# sensor.net
KiCad netlist of a schematic drawn in Altium Designer
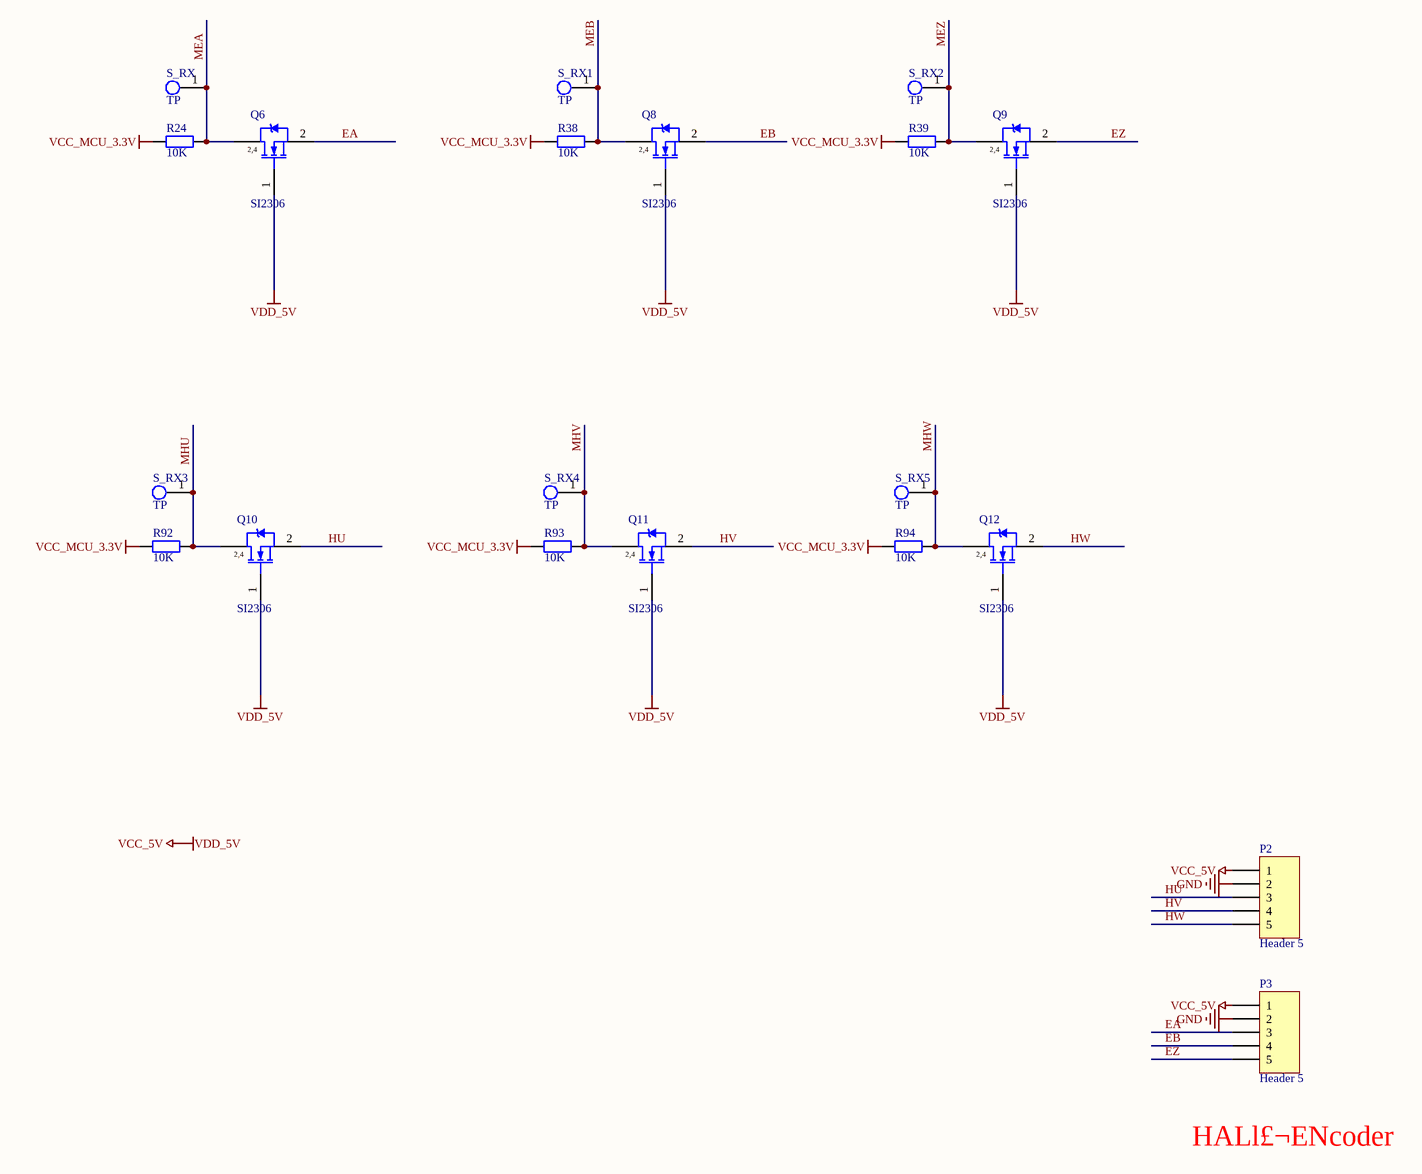
[diagram p0: sensor.SchDoc]

(export (version "E")
  (design (tool "Eeschema 10.0.6"))
  (components
    (comp (ref "P2")
      (value "Header 5")
      (footprint "HDR1X5")
      (description "Header, 5-Pin")
      (fields (field (name "PUBLISHER") "Altium Limited"))
      (libsource (lib "Miscellaneous Connectors") (part "Header 5"))
    )
    (comp (ref "P3")
      (value "Header 5")
      (footprint "HDR1X5")
      (description "Header, 5-Pin")
      (fields (field (name "PUBLISHER") "Altium Limited"))
      (libsource (lib "Miscellaneous Connectors") (part "Header 5"))
    )
    (comp (ref "Q6")
      (value "SI2306")
      (footprint "Pcblib_20110825:SOT23-3")
      (description "BUK92150-55A")
      (fields (field (name "PUBLISHER") "Altium Limited"))
      (libsource (lib "Schlib1") (part "BUK92150-55A"))
    )
    (comp (ref "Q8")
      (value "SI2306")
      (footprint "SOT23-3")
      (description "BUK92150-55A")
      (fields (field (name "PUBLISHER") "Altium Limited"))
      (libsource (lib "Schlib1") (part "BUK92150-55A"))
    )
    (comp (ref "Q9")
      (value "SI2306")
      (footprint "Pcblib_20110825:SOT23-3")
      (description "BUK92150-55A")
      (fields (field (name "PUBLISHER") "Altium Limited"))
      (libsource (lib "Schlib1") (part "BUK92150-55A"))
    )
    (comp (ref "Q10")
      (value "SI2306")
      (footprint "Pcblib_20110825:SOT23-3")
      (description "BUK92150-55A")
      (fields (field (name "PUBLISHER") "Altium Limited"))
      (libsource (lib "Schlib1") (part "BUK92150-55A"))
    )
    (comp (ref "Q11")
      (value "SI2306")
      (footprint "Pcblib_20110825:SOT23-3")
      (description "BUK92150-55A")
      (fields (field (name "PUBLISHER") "Altium Limited"))
      (libsource (lib "Schlib1") (part "BUK92150-55A"))
    )
    (comp (ref "Q12")
      (value "SI2306")
      (footprint "Pcblib_20110825:SOT23-3")
      (description "BUK92150-55A")
      (fields (field (name "PUBLISHER") "Altium Limited"))
      (libsource (lib "Schlib1") (part "BUK92150-55A"))
    )
    (comp (ref "R24")
      (value "10K")
      (footprint "Pcblib_20110825:0603R")
      (description "Resistor")
      (fields (field (name "PUBLISHER") "Altium Limited"))
      (libsource (lib "Miscellaneous Devices") (part "Res2"))
    )
    (comp (ref "R38")
      (value "10K")
      (footprint "Pcblib_20110825:0603R")
      (description "Resistor")
      (fields (field (name "PUBLISHER") "Altium Limited"))
      (libsource (lib "Miscellaneous Devices") (part "Res2"))
    )
    (comp (ref "R39")
      (value "10K")
      (footprint "Pcblib_20110825:0603R")
      (description "Resistor")
      (fields (field (name "PUBLISHER") "Altium Limited"))
      (libsource (lib "Miscellaneous Devices") (part "Res2"))
    )
    (comp (ref "R92")
      (value "10K")
      (footprint "Pcblib_20110825:0603R")
      (description "Resistor")
      (fields (field (name "PUBLISHER") "Altium Limited"))
      (libsource (lib "Miscellaneous Devices") (part "Res2"))
    )
    (comp (ref "R93")
      (value "10K")
      (footprint "Pcblib_20110825:0603R")
      (description "Resistor")
      (fields (field (name "PUBLISHER") "Altium Limited"))
      (libsource (lib "Miscellaneous Devices") (part "Res2"))
    )
    (comp (ref "R94")
      (value "10K")
      (footprint "Pcblib_20110825:0603R")
      (description "Resistor")
      (fields (field (name "PUBLISHER") "Altium Limited"))
      (libsource (lib "Miscellaneous Devices") (part "Res2"))
    )
    (comp (ref "S_RX")
      (value "TP")
      (footprint "Pcblib_20110825:TPD")
      (libsource (lib "Schlib_20110825") (part "TP"))
    )
    (comp (ref "S_RX1")
      (value "TP")
      (footprint "Pcblib_20110825:TPD")
      (libsource (lib "Schlib_20110825") (part "TP"))
    )
    (comp (ref "S_RX2")
      (value "TP")
      (footprint "Pcblib_20110825:TPD")
      (libsource (lib "Schlib_20110825") (part "TP"))
    )
    (comp (ref "S_RX3")
      (value "TP")
      (footprint "Pcblib_20110825:TPD")
      (libsource (lib "Schlib_20110825") (part "TP"))
    )
    (comp (ref "S_RX4")
      (value "TP")
      (footprint "Pcblib_20110825:TPD")
      (libsource (lib "Schlib_20110825") (part "TP"))
    )
    (comp (ref "S_RX5")
      (value "TP")
      (footprint "Pcblib_20110825:TPD")
      (libsource (lib "Schlib_20110825") (part "TP"))
    )
  )
  (nets
    (net (code "1") (name "/EA") (class "Default")
      (node (ref "P3") (pin "3") (pinfunction "3_3") (pintype "passive"))
      (node (ref "Q6") (pin "2") (pinfunction "S_2") (pintype "passive"))
    )
    (net (code "2") (name "/EB") (class "Default")
      (node (ref "P3") (pin "4") (pinfunction "4_4") (pintype "passive"))
      (node (ref "Q8") (pin "2") (pinfunction "S_2") (pintype "passive"))
    )
    (net (code "3") (name "/EZ") (class "Default")
      (node (ref "P3") (pin "5") (pinfunction "5_5") (pintype "passive"))
      (node (ref "Q9") (pin "2") (pinfunction "S_2") (pintype "passive"))
    )
    (net (code "4") (name "/HU") (class "Default")
      (node (ref "P2") (pin "3") (pinfunction "3_3") (pintype "passive"))
      (node (ref "Q10") (pin "2") (pinfunction "S_2") (pintype "passive"))
    )
    (net (code "5") (name "/HV") (class "Default")
      (node (ref "P2") (pin "4") (pinfunction "4_4") (pintype "passive"))
      (node (ref "Q11") (pin "2") (pinfunction "S_2") (pintype "passive"))
    )
    (net (code "6") (name "/HW") (class "Default")
      (node (ref "P2") (pin "5") (pinfunction "5_5") (pintype "passive"))
      (node (ref "Q12") (pin "2") (pinfunction "S_2") (pintype "passive"))
    )
    (net (code "7") (name "/MEA") (class "Default")
      (node (ref "Q6") (pin "3") (pinfunction "D_3") (pintype "passive"))
      (node (ref "R24") (pin "2") (pinfunction "2_2") (pintype "passive"))
      (node (ref "S_RX") (pin "1") (pintype "passive"))
    )
    (net (code "8") (name "/MEB") (class "Default")
      (node (ref "Q8") (pin "3") (pinfunction "D_3") (pintype "passive"))
      (node (ref "R38") (pin "2") (pinfunction "2_2") (pintype "passive"))
      (node (ref "S_RX1") (pin "1") (pintype "passive"))
    )
    (net (code "9") (name "/MEZ") (class "Default")
      (node (ref "Q9") (pin "3") (pinfunction "D_3") (pintype "passive"))
      (node (ref "R39") (pin "2") (pinfunction "2_2") (pintype "passive"))
      (node (ref "S_RX2") (pin "1") (pintype "passive"))
    )
    (net (code "10") (name "/MHU") (class "Default")
      (node (ref "Q10") (pin "3") (pinfunction "D_3") (pintype "passive"))
      (node (ref "R92") (pin "2") (pinfunction "2_2") (pintype "passive"))
      (node (ref "S_RX3") (pin "1") (pintype "passive"))
    )
    (net (code "11") (name "/MHV") (class "Default")
      (node (ref "Q11") (pin "3") (pinfunction "D_3") (pintype "passive"))
      (node (ref "R93") (pin "2") (pinfunction "2_2") (pintype "passive"))
      (node (ref "S_RX4") (pin "1") (pintype "passive"))
    )
    (net (code "12") (name "/MHW") (class "Default")
      (node (ref "Q12") (pin "3") (pinfunction "D_3") (pintype "passive"))
      (node (ref "R94") (pin "2") (pinfunction "2_2") (pintype "passive"))
      (node (ref "S_RX5") (pin "1") (pintype "passive"))
    )
    (net (code "13") (name "GND") (class "Default")
      (node (ref "P2") (pin "2") (pinfunction "2_2") (pintype "passive"))
      (node (ref "P3") (pin "2") (pinfunction "2_2") (pintype "passive"))
    )
    (net (code "14") (name "VCC_5V") (class "Default")
      (node (ref "P2") (pin "1") (pinfunction "1_1") (pintype "passive"))
      (node (ref "P3") (pin "1") (pinfunction "1_1") (pintype "passive"))
      (node (ref "Q10") (pin "1") (pinfunction "G_1") (pintype "passive"))
      (node (ref "Q11") (pin "1") (pinfunction "G_1") (pintype "passive"))
      (node (ref "Q12") (pin "1") (pinfunction "G_1") (pintype "passive"))
      (node (ref "Q6") (pin "1") (pinfunction "G_1") (pintype "passive"))
      (node (ref "Q8") (pin "1") (pinfunction "G_1") (pintype "passive"))
      (node (ref "Q9") (pin "1") (pinfunction "G_1") (pintype "passive"))
    )
    (net (code "15") (name "VCC_MCU_3.3V") (class "Default")
      (node (ref "R24") (pin "1") (pinfunction "1_1") (pintype "passive"))
      (node (ref "R38") (pin "1") (pinfunction "1_1") (pintype "passive"))
      (node (ref "R39") (pin "1") (pinfunction "1_1") (pintype "passive"))
      (node (ref "R92") (pin "1") (pinfunction "1_1") (pintype "passive"))
      (node (ref "R93") (pin "1") (pinfunction "1_1") (pintype "passive"))
      (node (ref "R94") (pin "1") (pinfunction "1_1") (pintype "passive"))
    )
  )
)
